# 20_DC_Link.net
KiCad netlist of a schematic drawn in Altium Designer
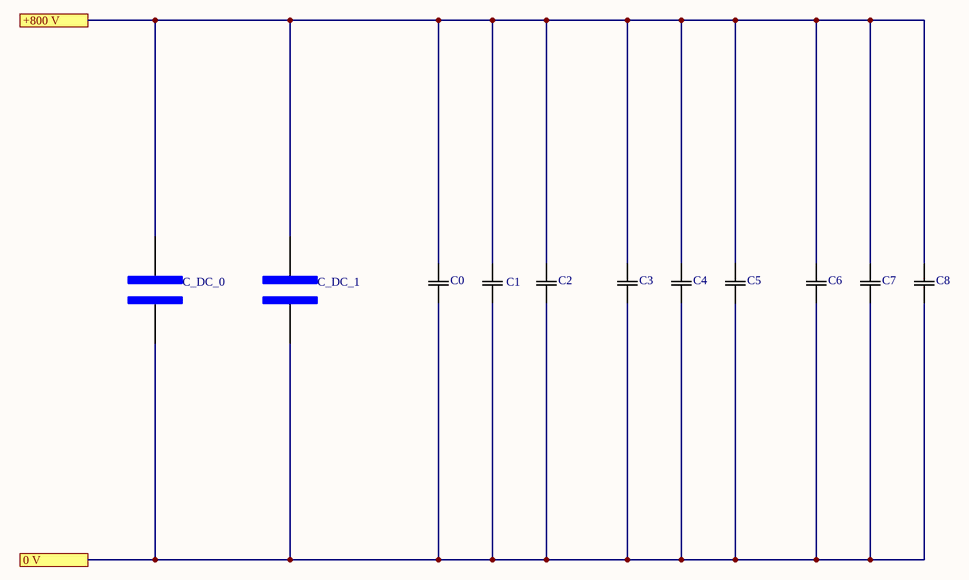
[diagram p0: 20_DC_Link.SchDoc]

(export (version "E")
  (design (tool "Eeschema 10.0.6"))
  (components
    (comp (ref "C0")
      (value "2220Y1K00474KETWS2")
      (footprint "CAP_2220Y_KNO")
      (description "Description")
      (fields (field (name "COPYRIGHT") "Copyright (C) 2026 Ultra Librarian. All rights reserved."))
      (libsource (lib "2220Y1K00474KETWS2") (part "2220Y1K00474KETWS2"))
    )
    (comp (ref "C1")
      (value "2220Y1K00474KETWS2")
      (footprint "CAP_2220Y_KNO")
      (description "Description")
      (fields (field (name "COPYRIGHT") "Copyright (C) 2026 Ultra Librarian. All rights reserved."))
      (libsource (lib "2220Y1K00474KETWS2") (part "2220Y1K00474KETWS2"))
    )
    (comp (ref "C2")
      (value "2220Y1K00474KETWS2")
      (footprint "CAP_2220Y_KNO")
      (description "Description")
      (fields (field (name "COPYRIGHT") "Copyright (C) 2026 Ultra Librarian. All rights reserved."))
      (libsource (lib "2220Y1K00474KETWS2") (part "2220Y1K00474KETWS2"))
    )
    (comp (ref "C3")
      (value "2220Y1K00474KETWS2")
      (footprint "CAP_2220Y_KNO")
      (description "Description")
      (fields (field (name "COPYRIGHT") "Copyright (C) 2026 Ultra Librarian. All rights reserved."))
      (libsource (lib "2220Y1K00474KETWS2") (part "2220Y1K00474KETWS2"))
    )
    (comp (ref "C4")
      (value "2220Y1K00474KETWS2")
      (footprint "CAP_2220Y_KNO")
      (description "Description")
      (fields (field (name "COPYRIGHT") "Copyright (C) 2026 Ultra Librarian. All rights reserved."))
      (libsource (lib "2220Y1K00474KETWS2") (part "2220Y1K00474KETWS2"))
    )
    (comp (ref "C5")
      (value "2220Y1K00474KETWS2")
      (footprint "CAP_2220Y_KNO")
      (description "Description")
      (fields (field (name "COPYRIGHT") "Copyright (C) 2026 Ultra Librarian. All rights reserved."))
      (libsource (lib "2220Y1K00474KETWS2") (part "2220Y1K00474KETWS2"))
    )
    (comp (ref "C6")
      (value "2220Y1K00474KETWS2")
      (footprint "CAP_2220Y_KNO")
      (description "Description")
      (fields (field (name "COPYRIGHT") "Copyright (C) 2026 Ultra Librarian. All rights reserved."))
      (libsource (lib "2220Y1K00474KETWS2") (part "2220Y1K00474KETWS2"))
    )
    (comp (ref "C7")
      (value "2220Y1K00474KETWS2")
      (footprint "CAP_2220Y_KNO")
      (description "Description")
      (fields (field (name "COPYRIGHT") "Copyright (C) 2026 Ultra Librarian. All rights reserved."))
      (libsource (lib "2220Y1K00474KETWS2") (part "2220Y1K00474KETWS2"))
    )
    (comp (ref "C8")
      (value "2220Y1K00474KETWS2")
      (footprint "CAP_2220Y_KNO")
      (description "Description")
      (fields (field (name "COPYRIGHT") "Copyright (C) 2026 Ultra Librarian. All rights reserved."))
      (libsource (lib "2220Y1K00474KETWS2") (part "2220Y1K00474KETWS2"))
    )
    (comp (ref "C_DC_0")
      (value "B25654A6177K001")
      (footprint "B25654A6177K001")
      (libsource (lib "B25654A9756K001") (part "B25654A6177K001"))
    )
    (comp (ref "C_DC_1")
      (value "B25654A6177K001")
      (footprint "B25654A6177K001")
      (libsource (lib "B25654A9756K001") (part "B25654A6177K001"))
    )
  )
  (nets
    (net (code "1") (name "/+800 V") (class "Default")
      (node (ref "C0") (pin "2") (pinfunction "2_2") (pintype "passive"))
      (node (ref "C1") (pin "2") (pinfunction "2_2") (pintype "passive"))
      (node (ref "C2") (pin "2") (pinfunction "2_2") (pintype "passive"))
      (node (ref "C3") (pin "2") (pinfunction "2_2") (pintype "passive"))
      (node (ref "C4") (pin "2") (pinfunction "2_2") (pintype "passive"))
      (node (ref "C5") (pin "2") (pinfunction "2_2") (pintype "passive"))
      (node (ref "C6") (pin "2") (pinfunction "2_2") (pintype "passive"))
      (node (ref "C7") (pin "2") (pinfunction "2_2") (pintype "passive"))
      (node (ref "C8") (pin "2") (pinfunction "2_2") (pintype "passive"))
      (node (ref "C_DC_0") (pin "1") (pinfunction "1_1") (pintype "passive"))
      (node (ref "C_DC_1") (pin "1") (pinfunction "1_1") (pintype "passive"))
    )
    (net (code "2") (name "/0 V") (class "Default")
      (node (ref "C0") (pin "1") (pinfunction "1_1") (pintype "passive"))
      (node (ref "C1") (pin "1") (pinfunction "1_1") (pintype "passive"))
      (node (ref "C2") (pin "1") (pinfunction "1_1") (pintype "passive"))
      (node (ref "C3") (pin "1") (pinfunction "1_1") (pintype "passive"))
      (node (ref "C4") (pin "1") (pinfunction "1_1") (pintype "passive"))
      (node (ref "C5") (pin "1") (pinfunction "1_1") (pintype "passive"))
      (node (ref "C6") (pin "1") (pinfunction "1_1") (pintype "passive"))
      (node (ref "C7") (pin "1") (pinfunction "1_1") (pintype "passive"))
      (node (ref "C8") (pin "1") (pinfunction "1_1") (pintype "passive"))
      (node (ref "C_DC_0") (pin "2") (pinfunction "2_2") (pintype "passive"))
      (node (ref "C_DC_1") (pin "2") (pinfunction "2_2") (pintype "passive"))
    )
  )
)
